# Strain_Gauges_Amplifier_SMD.net
KiCad netlist of a schematic drawn in EAGLE
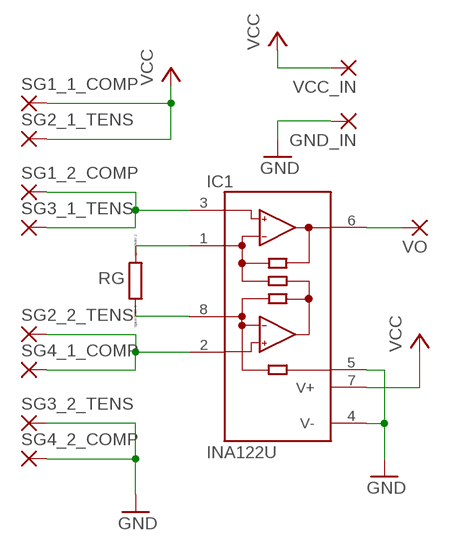
[diagram p0: schematic, sheet 1]

(export (version "E")
  (design (tool "Eeschema 10.0.6"))
  (components
    (comp (ref "GND_IN")
      (value "SMD2")
      (footprint "eagle-import:SMD1,27-2,54")
      (libsource (lib "eagle-import") (part "SMD2"))
    )
    (comp (ref "IC1")
      (value "INA122U")
      (footprint "eagle-import:SO08")
      (libsource (lib "eagle-import") (part "INA122U"))
    )
    (comp (ref "RG") (value "R") (footprint "eagle-import:R0805") (libsource (lib "eagle-import") (part "R")))
    (comp (ref "SG1_1_COMP")
      (value "SMD2")
      (footprint "eagle-import:SMD1,27-2,54")
      (libsource (lib "eagle-import") (part "SMD2"))
    )
    (comp (ref "SG1_2_COMP")
      (value "SMD2")
      (footprint "eagle-import:SMD1,27-2,54")
      (libsource (lib "eagle-import") (part "SMD2"))
    )
    (comp (ref "SG2_1_TENS")
      (value "SMD2")
      (footprint "eagle-import:SMD1,27-2,54")
      (libsource (lib "eagle-import") (part "SMD2"))
    )
    (comp (ref "SG2_2_TENS")
      (value "SMD2")
      (footprint "eagle-import:SMD1,27-2,54")
      (libsource (lib "eagle-import") (part "SMD2"))
    )
    (comp (ref "SG3_1_TENS")
      (value "SMD2")
      (footprint "eagle-import:SMD1,27-2,54")
      (libsource (lib "eagle-import") (part "SMD2"))
    )
    (comp (ref "SG3_2_TENS")
      (value "SMD2")
      (footprint "eagle-import:SMD1,27-2,54")
      (libsource (lib "eagle-import") (part "SMD2"))
    )
    (comp (ref "SG4_1_COMP")
      (value "SMD2")
      (footprint "eagle-import:SMD1,27-2,54")
      (libsource (lib "eagle-import") (part "SMD2"))
    )
    (comp (ref "SG4_2_COMP")
      (value "SMD2")
      (footprint "eagle-import:SMD1,27-2,54")
      (libsource (lib "eagle-import") (part "SMD2"))
    )
    (comp (ref "VCC_IN")
      (value "SMD2")
      (footprint "eagle-import:SMD1,27-2,54")
      (libsource (lib "eagle-import") (part "SMD2"))
    )
    (comp (ref "VO")
      (value "SMD2")
      (footprint "eagle-import:SMD1,27-2,54")
      (libsource (lib "eagle-import") (part "SMD2"))
    )
  )
  (nets
    (net (code "1") (name "GND") (class "Default")
      (node (ref "GND_IN") (pin "1") (pinfunction "P_1") (pintype "passive"))
      (node (ref "IC1") (pin "4") (pinfunction "V-_4") (pintype "power_in"))
      (node (ref "IC1") (pin "5") (pinfunction "REF_5") (pintype "passive"))
      (node (ref "SG3_2_TENS") (pin "1") (pinfunction "P_1") (pintype "passive"))
      (node (ref "SG4_2_COMP") (pin "1") (pinfunction "P_1") (pintype "passive"))
    )
    (net (code "2") (name "Net-(IC1-+IN)") (class "Default")
      (node (ref "IC1") (pin "3") (pinfunction "+IN_3") (pintype "input"))
      (node (ref "SG1_2_COMP") (pin "1") (pinfunction "P_1") (pintype "passive"))
      (node (ref "SG3_1_TENS") (pin "1") (pinfunction "P_1") (pintype "passive"))
    )
    (net (code "3") (name "Net-(IC1--IN)") (class "Default")
      (node (ref "IC1") (pin "2") (pinfunction "-IN_2") (pintype "input"))
      (node (ref "SG2_2_TENS") (pin "1") (pinfunction "P_1") (pintype "passive"))
      (node (ref "SG4_1_COMP") (pin "1") (pinfunction "P_1") (pintype "passive"))
    )
    (net (code "4") (name "Net-(IC1-OUT)") (class "Default")
      (node (ref "IC1") (pin "6") (pinfunction "OUT_6") (pintype "output"))
      (node (ref "VO") (pin "1") (pinfunction "P_1") (pintype "passive"))
    )
    (net (code "5") (name "Net-(IC1-RG-Pad1)") (class "Default")
      (node (ref "IC1") (pin "1") (pinfunction "RG_1") (pintype "passive"))
      (node (ref "RG") (pin "2") (pinfunction "2_2") (pintype "passive"))
    )
    (net (code "6") (name "Net-(IC1-RG-Pad8)") (class "Default")
      (node (ref "IC1") (pin "8") (pinfunction "RG_8") (pintype "passive"))
      (node (ref "RG") (pin "1") (pinfunction "1_1") (pintype "passive"))
    )
    (net (code "7") (name "VCC") (class "Default")
      (node (ref "IC1") (pin "7") (pinfunction "V+_7") (pintype "power_in"))
      (node (ref "SG1_1_COMP") (pin "1") (pinfunction "P_1") (pintype "passive"))
      (node (ref "SG2_1_TENS") (pin "1") (pinfunction "P_1") (pintype "passive"))
      (node (ref "VCC_IN") (pin "1") (pinfunction "P_1") (pintype "passive"))
    )
  )
)
